# CAN-Breakout.net
KiCad netlist of a schematic drawn in EasyEDA
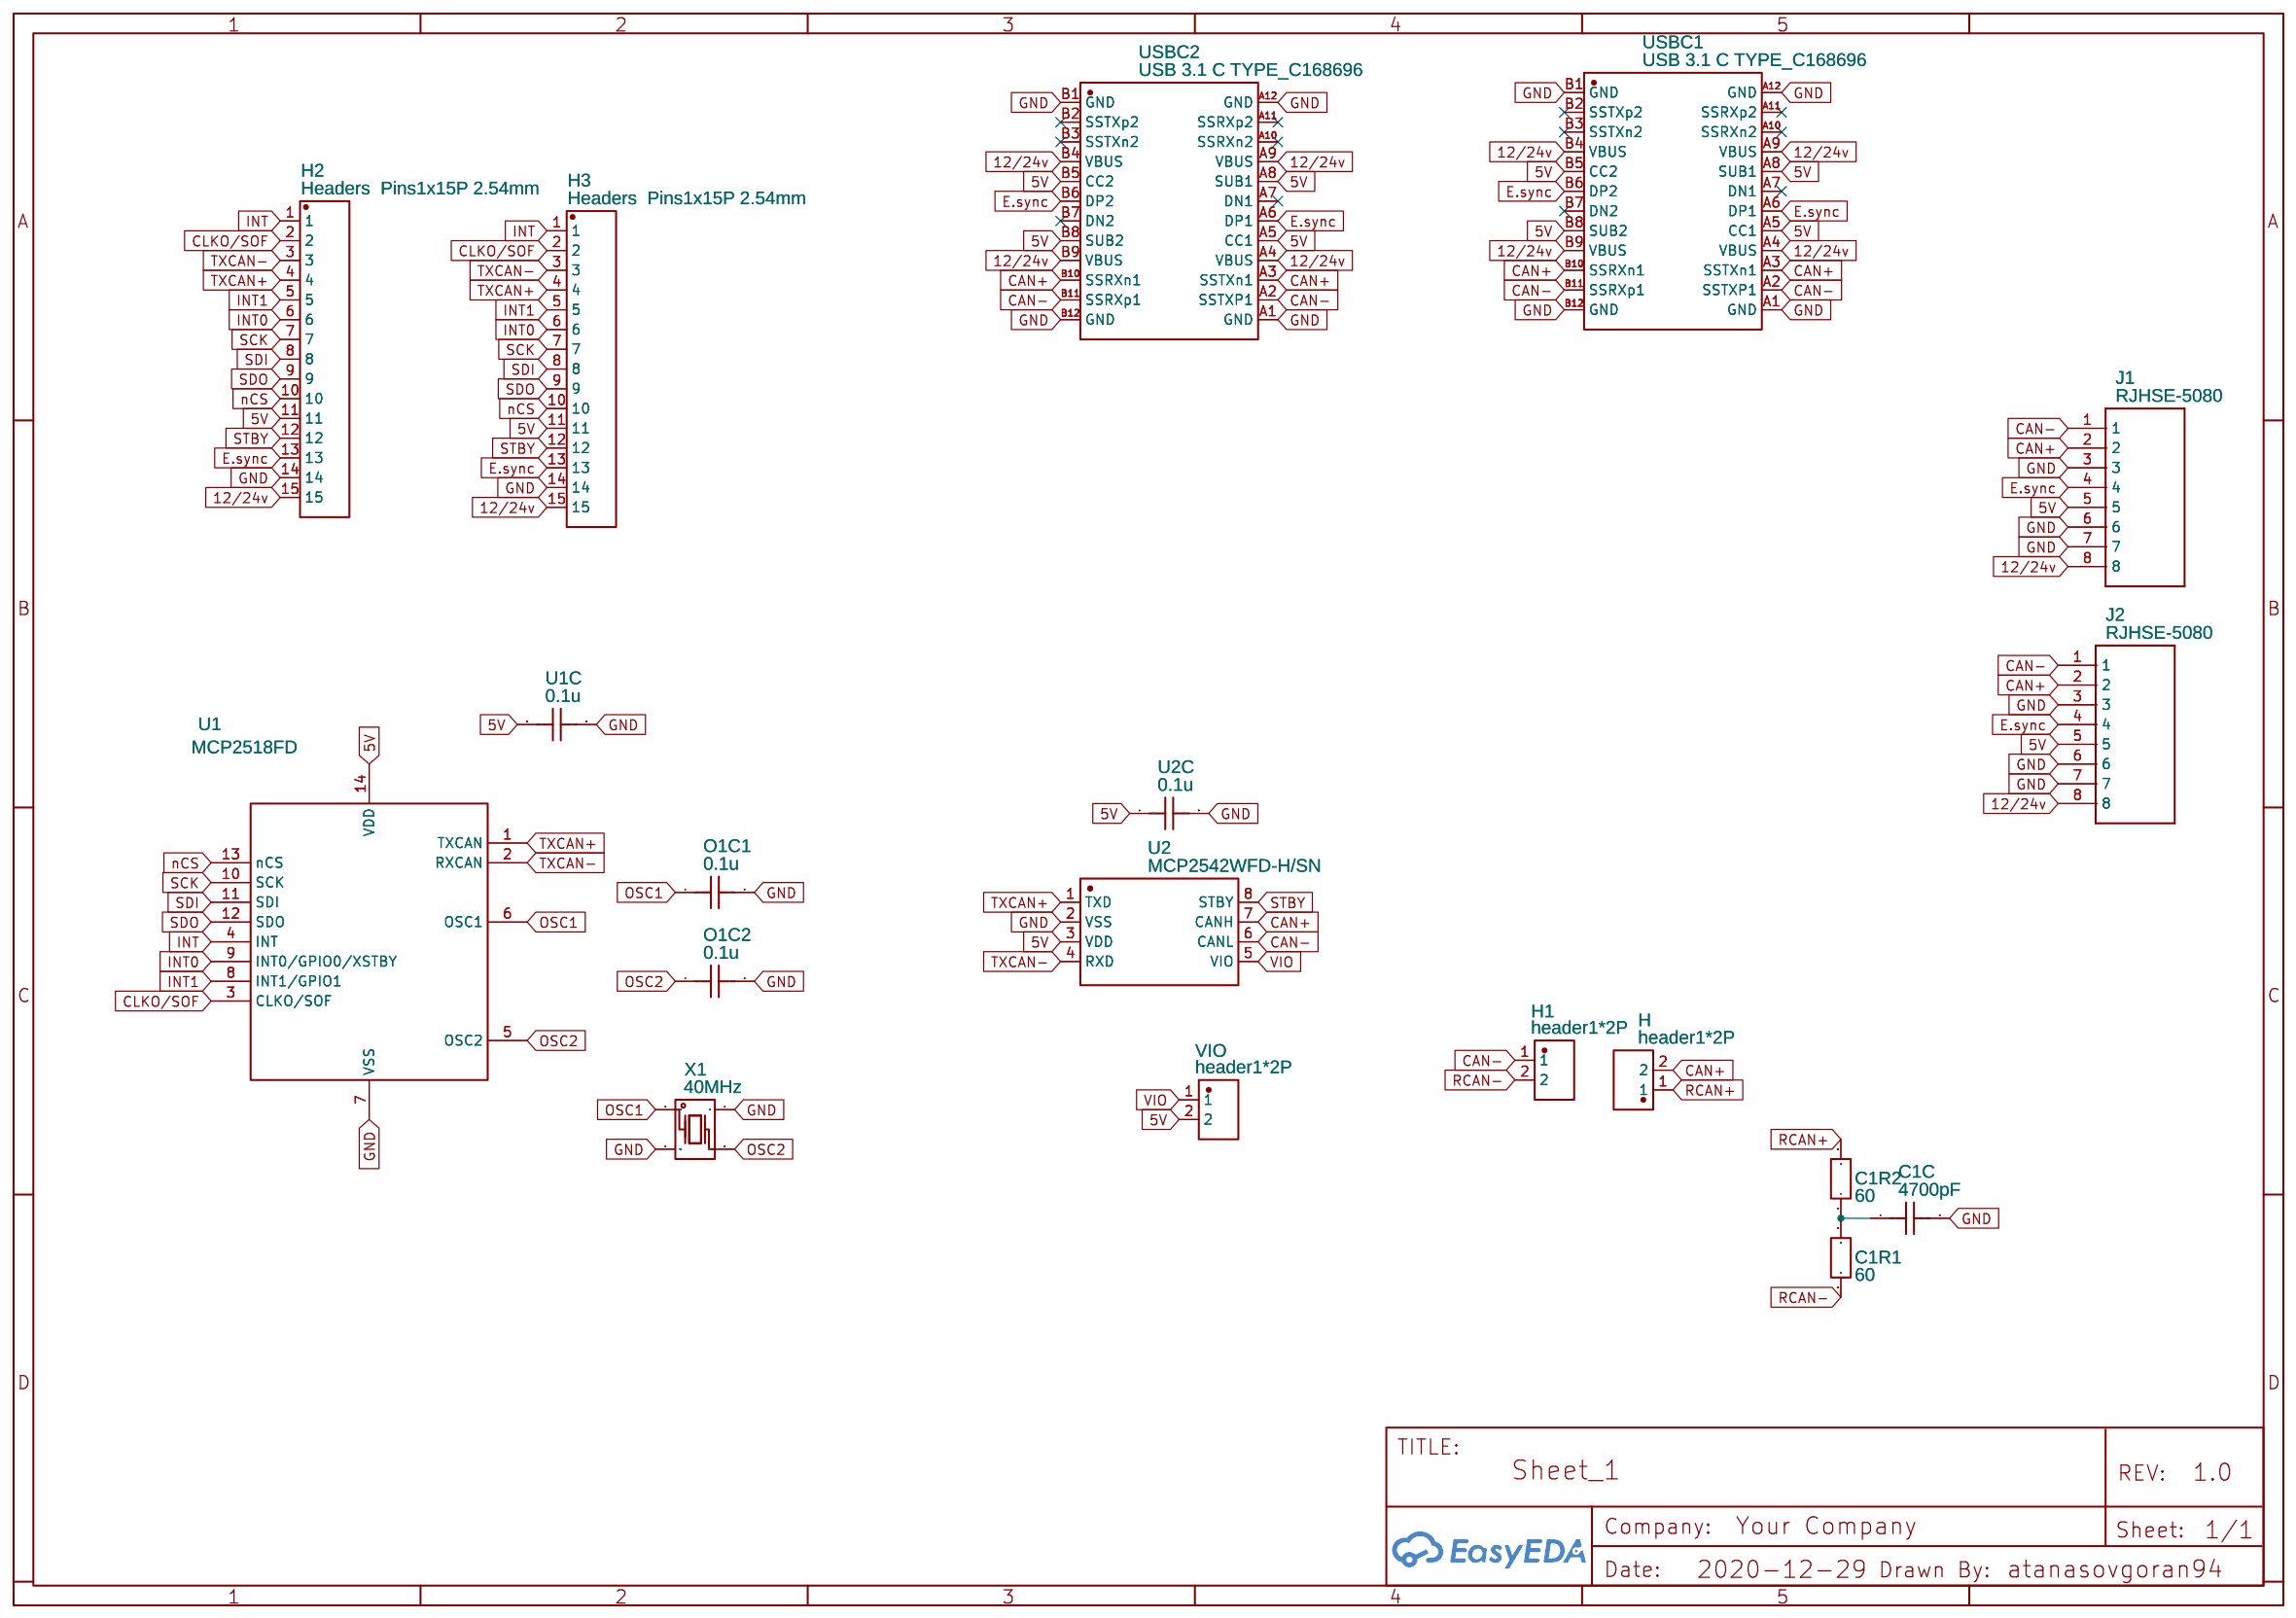
[diagram p0: schematic sheet]

(export (version "E")
  (design (tool "Eeschema 10.0.6"))
  (components
    (comp (ref "C1C") (value "4700pF") (libsource (lib "") (part "C_0402_US_3")))
    (comp (ref "C1R1") (value "60") (libsource (lib "") (part "R_0402_EU")))
    (comp (ref "C1R2") (value "60") (libsource (lib "") (part "R_0402_EU")))
    (comp (ref "H")
      (value "header1*2P")
      (fields
        (field (name "BOM_Manufacturer Part") "Female header1*2P")
        (field (name "BOM_Supplier Part") "C66509")
      )
      (libsource (lib "") (part "Female header1*2P_1"))
    )
    (comp (ref "H1")
      (value "header1*2P")
      (fields
        (field (name "BOM_Manufacturer Part") "Female header1*2P")
        (field (name "BOM_Supplier Part") "C66509")
      )
      (libsource (lib "") (part "Female header1*2P_2"))
    )
    (comp (ref "H2")
      (value "Headers  Pins1x15P 2.54mm")
      (fields (field (name "BOM_Supplier Part") "C54102"))
      (libsource (lib "") (part "Headers  Pins1x15P 2.54mm"))
    )
    (comp (ref "H3")
      (value "Headers  Pins1x15P 2.54mm")
      (fields (field (name "BOM_Supplier Part") "C54102"))
      (libsource (lib "") (part "Headers  Pins1x15P 2.54mm"))
    )
    (comp (ref "J1") (value "RJHSE-5080") (libsource (lib "") (part "RJHSE-5080")))
    (comp (ref "J2") (value "RJHSE-5080") (libsource (lib "") (part "RJHSE-5080")))
    (comp (ref "O1C1") (value "0.1u") (libsource (lib "") (part "C_0402_US")))
    (comp (ref "O1C2") (value "0.1u") (libsource (lib "") (part "C_0402_US")))
    (comp (ref "U1") (value "MCP2518FD") (libsource (lib "") (part "MCP2518FD")))
    (comp (ref "U1C") (value "0.1u") (libsource (lib "") (part "C_0402_US_1")))
    (comp (ref "U2")
      (value "MCP2542WFD-H/SN")
      (fields (field (name "BOM_Supplier Part") "C144310"))
      (libsource (lib "") (part "MCP2542WFD-H/SN"))
    )
    (comp (ref "U2C") (value "0.1u") (libsource (lib "") (part "C_0402_US_2")))
    (comp (ref "USBC1")
      (value "USB 3.1 C TYPE_C168696")
      (fields (field (name "BOM_Supplier Part") "C168696"))
      (libsource (lib "") (part "USB 3.1 C TYPE_C168696"))
    )
    (comp (ref "USBC2")
      (value "USB 3.1 C TYPE_C168696")
      (fields (field (name "BOM_Supplier Part") "C168696"))
      (libsource (lib "") (part "USB 3.1 C TYPE_C168696"))
    )
    (comp (ref "VIO")
      (value "header1*2P")
      (fields
        (field (name "BOM_Manufacturer Part") "Female header1*2P")
        (field (name "BOM_Supplier Part") "C66509")
      )
      (libsource (lib "") (part "Female header1*2P"))
    )
    (comp (ref "X1")
      (value "40MHz")
      (fields
        (field (name "BOM_Manufacturer Part") "ECX-2236BSMD CRYSTAL")
        (field (name "BOM_Supplier Part") "C389786")
      )
      (libsource (lib "") (part "ECX-2236B SMD CRYSTAL"))
    )
  )
  (nets
    (net (code "1") (name "5V") (class "Default")
      (node (ref "H2") (pin "11") (pinfunction "11_11") (pintype "unspecified"))
      (node (ref "H3") (pin "11") (pinfunction "11_11") (pintype "unspecified"))
      (node (ref "J1") (pin "5") (pinfunction "5_5") (pintype "bidirectional"))
      (node (ref "J2") (pin "5") (pinfunction "5_5") (pintype "bidirectional"))
      (node (ref "U1") (pin "14") (pinfunction "VDD_14") (pintype "unspecified"))
      (node (ref "U1C") (pin "1") (pinfunction "1_1") (pintype "unspecified"))
      (node (ref "U2") (pin "3") (pinfunction "VDD_3") (pintype "unspecified"))
      (node (ref "U2C") (pin "1") (pinfunction "1_1") (pintype "unspecified"))
      (node (ref "USBC1") (pin "A5") (pinfunction "CC1_A5") (pintype "unspecified"))
      (node (ref "USBC1") (pin "A8") (pinfunction "SUB1_A8") (pintype "unspecified"))
      (node (ref "USBC1") (pin "B5") (pinfunction "CC2_B5") (pintype "unspecified"))
      (node (ref "USBC1") (pin "B8") (pinfunction "SUB2_B8") (pintype "unspecified"))
      (node (ref "USBC2") (pin "A5") (pinfunction "CC1_A5") (pintype "unspecified"))
      (node (ref "USBC2") (pin "A8") (pinfunction "SUB1_A8") (pintype "unspecified"))
      (node (ref "USBC2") (pin "B5") (pinfunction "CC2_B5") (pintype "unspecified"))
      (node (ref "USBC2") (pin "B8") (pinfunction "SUB2_B8") (pintype "unspecified"))
      (node (ref "VIO") (pin "2") (pinfunction "2_2") (pintype "unspecified"))
    )
    (net (code "2") (name "12{slash}24v") (class "Default")
      (node (ref "H2") (pin "15") (pinfunction "15_15") (pintype "unspecified"))
      (node (ref "H3") (pin "15") (pinfunction "15_15") (pintype "unspecified"))
      (node (ref "J1") (pin "8") (pinfunction "8_8") (pintype "bidirectional"))
      (node (ref "J2") (pin "8") (pinfunction "8_8") (pintype "bidirectional"))
      (node (ref "USBC1") (pin "A4") (pinfunction "VBUS_A4") (pintype "unspecified"))
      (node (ref "USBC1") (pin "A9") (pinfunction "VBUS_A9") (pintype "unspecified"))
      (node (ref "USBC1") (pin "B4") (pinfunction "VBUS_B4") (pintype "unspecified"))
      (node (ref "USBC1") (pin "B9") (pinfunction "VBUS_B9") (pintype "unspecified"))
      (node (ref "USBC2") (pin "A4") (pinfunction "VBUS_A4") (pintype "unspecified"))
      (node (ref "USBC2") (pin "A9") (pinfunction "VBUS_A9") (pintype "unspecified"))
      (node (ref "USBC2") (pin "B4") (pinfunction "VBUS_B4") (pintype "unspecified"))
      (node (ref "USBC2") (pin "B9") (pinfunction "VBUS_B9") (pintype "unspecified"))
    )
    (net (code "3") (name "CAN+") (class "Default")
      (node (ref "H") (pin "2") (pinfunction "2_2") (pintype "unspecified"))
      (node (ref "J1") (pin "2") (pinfunction "2_2") (pintype "bidirectional"))
      (node (ref "J2") (pin "2") (pinfunction "2_2") (pintype "bidirectional"))
      (node (ref "U2") (pin "7") (pinfunction "CANH_7") (pintype "unspecified"))
      (node (ref "USBC1") (pin "A3") (pinfunction "SSTXn1_A3") (pintype "unspecified"))
      (node (ref "USBC1") (pin "B10") (pinfunction "SSRXn1_B10") (pintype "unspecified"))
      (node (ref "USBC2") (pin "A3") (pinfunction "SSTXn1_A3") (pintype "unspecified"))
      (node (ref "USBC2") (pin "B10") (pinfunction "SSRXn1_B10") (pintype "unspecified"))
    )
    (net (code "4") (name "CAN-") (class "Default")
      (node (ref "H1") (pin "1") (pinfunction "1_1") (pintype "unspecified"))
      (node (ref "J1") (pin "1") (pinfunction "1_1") (pintype "bidirectional"))
      (node (ref "J2") (pin "1") (pinfunction "1_1") (pintype "bidirectional"))
      (node (ref "U2") (pin "6") (pinfunction "CANL_6") (pintype "unspecified"))
      (node (ref "USBC1") (pin "A2") (pinfunction "SSTXP1_A2") (pintype "unspecified"))
      (node (ref "USBC1") (pin "B11") (pinfunction "SSRXp1_B11") (pintype "unspecified"))
      (node (ref "USBC2") (pin "A2") (pinfunction "SSTXP1_A2") (pintype "unspecified"))
      (node (ref "USBC2") (pin "B11") (pinfunction "SSRXp1_B11") (pintype "unspecified"))
    )
    (net (code "5") (name "CLKO{slash}SOF") (class "Default")
      (node (ref "H2") (pin "2") (pinfunction "2_2") (pintype "unspecified"))
      (node (ref "H3") (pin "2") (pinfunction "2_2") (pintype "unspecified"))
      (node (ref "U1") (pin "3") (pinfunction "CLKO/SOF_3") (pintype "unspecified"))
    )
    (net (code "6") (name "E.sync") (class "Default")
      (node (ref "H2") (pin "13") (pinfunction "13_13") (pintype "unspecified"))
      (node (ref "H3") (pin "13") (pinfunction "13_13") (pintype "unspecified"))
      (node (ref "J1") (pin "4") (pinfunction "4_4") (pintype "bidirectional"))
      (node (ref "J2") (pin "4") (pinfunction "4_4") (pintype "bidirectional"))
      (node (ref "USBC1") (pin "A6") (pinfunction "DP1_A6") (pintype "unspecified"))
      (node (ref "USBC1") (pin "B6") (pinfunction "DP2_B6") (pintype "unspecified"))
      (node (ref "USBC2") (pin "A6") (pinfunction "DP1_A6") (pintype "unspecified"))
      (node (ref "USBC2") (pin "B6") (pinfunction "DP2_B6") (pintype "unspecified"))
    )
    (net (code "7") (name "GND") (class "Default")
      (node (ref "C1C") (pin "2") (pinfunction "2_2") (pintype "unspecified"))
      (node (ref "H2") (pin "14") (pinfunction "14_14") (pintype "unspecified"))
      (node (ref "H3") (pin "14") (pinfunction "14_14") (pintype "unspecified"))
      (node (ref "J1") (pin "3") (pinfunction "3_3") (pintype "bidirectional"))
      (node (ref "J1") (pin "6") (pinfunction "6_6") (pintype "bidirectional"))
      (node (ref "J1") (pin "7") (pinfunction "7_7") (pintype "bidirectional"))
      (node (ref "J2") (pin "3") (pinfunction "3_3") (pintype "bidirectional"))
      (node (ref "J2") (pin "6") (pinfunction "6_6") (pintype "bidirectional"))
      (node (ref "J2") (pin "7") (pinfunction "7_7") (pintype "bidirectional"))
      (node (ref "O1C1") (pin "2") (pinfunction "2_2") (pintype "unspecified"))
      (node (ref "O1C2") (pin "2") (pinfunction "2_2") (pintype "unspecified"))
      (node (ref "U1") (pin "7") (pinfunction "VSS_7") (pintype "unspecified"))
      (node (ref "U1C") (pin "2") (pinfunction "2_2") (pintype "unspecified"))
      (node (ref "U2") (pin "2") (pinfunction "VSS_2") (pintype "unspecified"))
      (node (ref "U2C") (pin "2") (pinfunction "2_2") (pintype "unspecified"))
      (node (ref "USBC1") (pin "A1") (pinfunction "GND_A1") (pintype "unspecified"))
      (node (ref "USBC1") (pin "A12") (pinfunction "GND_A12") (pintype "unspecified"))
      (node (ref "USBC1") (pin "B1") (pinfunction "GND_B1") (pintype "unspecified"))
      (node (ref "USBC1") (pin "B12") (pinfunction "GND_B12") (pintype "unspecified"))
      (node (ref "USBC2") (pin "A1") (pinfunction "GND_A1") (pintype "unspecified"))
      (node (ref "USBC2") (pin "A12") (pinfunction "GND_A12") (pintype "unspecified"))
      (node (ref "USBC2") (pin "B1") (pinfunction "GND_B1") (pintype "unspecified"))
      (node (ref "USBC2") (pin "B12") (pinfunction "GND_B12") (pintype "unspecified"))
      (node (ref "X1") (pin "2") (pinfunction "GND_2") (pintype "input"))
      (node (ref "X1") (pin "4") (pinfunction "GND_4") (pintype "input"))
    )
    (net (code "8") (name "INT") (class "Default")
      (node (ref "H2") (pin "1") (pinfunction "1_1") (pintype "unspecified"))
      (node (ref "H3") (pin "1") (pinfunction "1_1") (pintype "unspecified"))
      (node (ref "U1") (pin "4") (pinfunction "INT_4") (pintype "unspecified"))
    )
    (net (code "9") (name "INT0") (class "Default")
      (node (ref "H2") (pin "6") (pinfunction "6_6") (pintype "unspecified"))
      (node (ref "H3") (pin "6") (pinfunction "6_6") (pintype "unspecified"))
      (node (ref "U1") (pin "9") (pinfunction "INT0/GPIO0/XSTBY_9") (pintype "unspecified"))
    )
    (net (code "10") (name "INT1") (class "Default")
      (node (ref "H2") (pin "5") (pinfunction "5_5") (pintype "unspecified"))
      (node (ref "H3") (pin "5") (pinfunction "5_5") (pintype "unspecified"))
      (node (ref "U1") (pin "8") (pinfunction "INT1/GPIO1_8") (pintype "unspecified"))
    )
    (net (code "11") (name "Net-(C1C-Pad1)") (class "Default")
      (node (ref "C1C") (pin "1") (pinfunction "1_1") (pintype "unspecified"))
      (node (ref "C1R1") (pin "2") (pinfunction "2_2") (pintype "unspecified"))
      (node (ref "C1R2") (pin "1") (pinfunction "1_1") (pintype "unspecified"))
    )
    (net (code "12") (name "OSC1") (class "Default")
      (node (ref "O1C1") (pin "1") (pinfunction "1_1") (pintype "unspecified"))
      (node (ref "U1") (pin "6") (pinfunction "OSC1_6") (pintype "unspecified"))
      (node (ref "X1") (pin "1") (pinfunction "IN-OUT_1") (pintype "input"))
    )
    (net (code "13") (name "OSC2") (class "Default")
      (node (ref "O1C2") (pin "1") (pinfunction "1_1") (pintype "unspecified"))
      (node (ref "U1") (pin "5") (pinfunction "OSC2_5") (pintype "unspecified"))
      (node (ref "X1") (pin "3") (pinfunction "OUT-IN_3") (pintype "input"))
    )
    (net (code "14") (name "RCAN+") (class "Default")
      (node (ref "C1R2") (pin "2") (pinfunction "2_2") (pintype "unspecified"))
      (node (ref "H") (pin "1") (pinfunction "1_1") (pintype "unspecified"))
    )
    (net (code "15") (name "RCAN-") (class "Default")
      (node (ref "C1R1") (pin "1") (pinfunction "1_1") (pintype "unspecified"))
      (node (ref "H1") (pin "2") (pinfunction "2_2") (pintype "unspecified"))
    )
    (net (code "16") (name "SCK") (class "Default")
      (node (ref "H2") (pin "7") (pinfunction "7_7") (pintype "unspecified"))
      (node (ref "H3") (pin "7") (pinfunction "7_7") (pintype "unspecified"))
      (node (ref "U1") (pin "10") (pinfunction "SCK_10") (pintype "unspecified"))
    )
    (net (code "17") (name "SDI") (class "Default")
      (node (ref "H2") (pin "8") (pinfunction "8_8") (pintype "unspecified"))
      (node (ref "H3") (pin "8") (pinfunction "8_8") (pintype "unspecified"))
      (node (ref "U1") (pin "11") (pinfunction "SDI_11") (pintype "unspecified"))
    )
    (net (code "18") (name "SDO") (class "Default")
      (node (ref "H2") (pin "9") (pinfunction "9_9") (pintype "unspecified"))
      (node (ref "H3") (pin "9") (pinfunction "9_9") (pintype "unspecified"))
      (node (ref "U1") (pin "12") (pinfunction "SDO_12") (pintype "unspecified"))
    )
    (net (code "19") (name "STBY") (class "Default")
      (node (ref "H2") (pin "12") (pinfunction "12_12") (pintype "unspecified"))
      (node (ref "H3") (pin "12") (pinfunction "12_12") (pintype "unspecified"))
      (node (ref "U2") (pin "8") (pinfunction "STBY_8") (pintype "unspecified"))
    )
    (net (code "20") (name "TXCAN+") (class "Default")
      (node (ref "H2") (pin "4") (pinfunction "4_4") (pintype "unspecified"))
      (node (ref "H3") (pin "4") (pinfunction "4_4") (pintype "unspecified"))
      (node (ref "U1") (pin "1") (pinfunction "TXCAN_1") (pintype "unspecified"))
      (node (ref "U2") (pin "1") (pinfunction "TXD_1") (pintype "unspecified"))
    )
    (net (code "21") (name "TXCAN-") (class "Default")
      (node (ref "H2") (pin "3") (pinfunction "3_3") (pintype "unspecified"))
      (node (ref "H3") (pin "3") (pinfunction "3_3") (pintype "unspecified"))
      (node (ref "U1") (pin "2") (pinfunction "RXCAN_2") (pintype "unspecified"))
      (node (ref "U2") (pin "4") (pinfunction "RXD_4") (pintype "unspecified"))
    )
    (net (code "22") (name "VIO") (class "Default")
      (node (ref "U2") (pin "5") (pinfunction "VIO_5") (pintype "unspecified"))
      (node (ref "VIO") (pin "1") (pinfunction "1_1") (pintype "unspecified"))
    )
    (net (code "23") (name "nCS") (class "Default")
      (node (ref "H2") (pin "10") (pinfunction "10_10") (pintype "unspecified"))
      (node (ref "H3") (pin "10") (pinfunction "10_10") (pintype "unspecified"))
      (node (ref "U1") (pin "13") (pinfunction "nCS_13") (pintype "unspecified"))
    )
    (net (code "24") (name "unconnected-(USBC1-DN1-PadA7)") (class "Default")
      (node (ref "USBC1") (pin "A7") (pinfunction "DN1_A7") (pintype "unspecified+no_connect"))
    )
    (net (code "25") (name "unconnected-(USBC1-DN2-PadB7)") (class "Default")
      (node (ref "USBC1") (pin "B7") (pinfunction "DN2_B7") (pintype "unspecified+no_connect"))
    )
    (net (code "26") (name "unconnected-(USBC1-SSRXn2-PadA10)") (class "Default")
      (node (ref "USBC1") (pin "A10") (pinfunction "SSRXn2_A10") (pintype "unspecified+no_connect"))
    )
    (net (code "27") (name "unconnected-(USBC1-SSRXp2-PadA11)") (class "Default")
      (node (ref "USBC1") (pin "A11") (pinfunction "SSRXp2_A11") (pintype "unspecified+no_connect"))
    )
    (net (code "28") (name "unconnected-(USBC1-SSTXn2-PadB3)") (class "Default")
      (node (ref "USBC1") (pin "B3") (pinfunction "SSTXn2_B3") (pintype "unspecified+no_connect"))
    )
    (net (code "29") (name "unconnected-(USBC1-SSTXp2-PadB2)") (class "Default")
      (node (ref "USBC1") (pin "B2") (pinfunction "SSTXp2_B2") (pintype "unspecified+no_connect"))
    )
    (net (code "30") (name "unconnected-(USBC2-DN1-PadA7)") (class "Default")
      (node (ref "USBC2") (pin "A7") (pinfunction "DN1_A7") (pintype "unspecified+no_connect"))
    )
    (net (code "31") (name "unconnected-(USBC2-DN2-PadB7)") (class "Default")
      (node (ref "USBC2") (pin "B7") (pinfunction "DN2_B7") (pintype "unspecified+no_connect"))
    )
    (net (code "32") (name "unconnected-(USBC2-SSRXn2-PadA10)") (class "Default")
      (node (ref "USBC2") (pin "A10") (pinfunction "SSRXn2_A10") (pintype "unspecified+no_connect"))
    )
    (net (code "33") (name "unconnected-(USBC2-SSRXp2-PadA11)") (class "Default")
      (node (ref "USBC2") (pin "A11") (pinfunction "SSRXp2_A11") (pintype "unspecified+no_connect"))
    )
    (net (code "34") (name "unconnected-(USBC2-SSTXn2-PadB3)") (class "Default")
      (node (ref "USBC2") (pin "B3") (pinfunction "SSTXn2_B3") (pintype "unspecified+no_connect"))
    )
    (net (code "35") (name "unconnected-(USBC2-SSTXp2-PadB2)") (class "Default")
      (node (ref "USBC2") (pin "B2") (pinfunction "SSTXp2_B2") (pintype "unspecified+no_connect"))
    )
  )
)
